# mcu_rev2_full.net
KiCad netlist of a schematic drawn in EAGLE
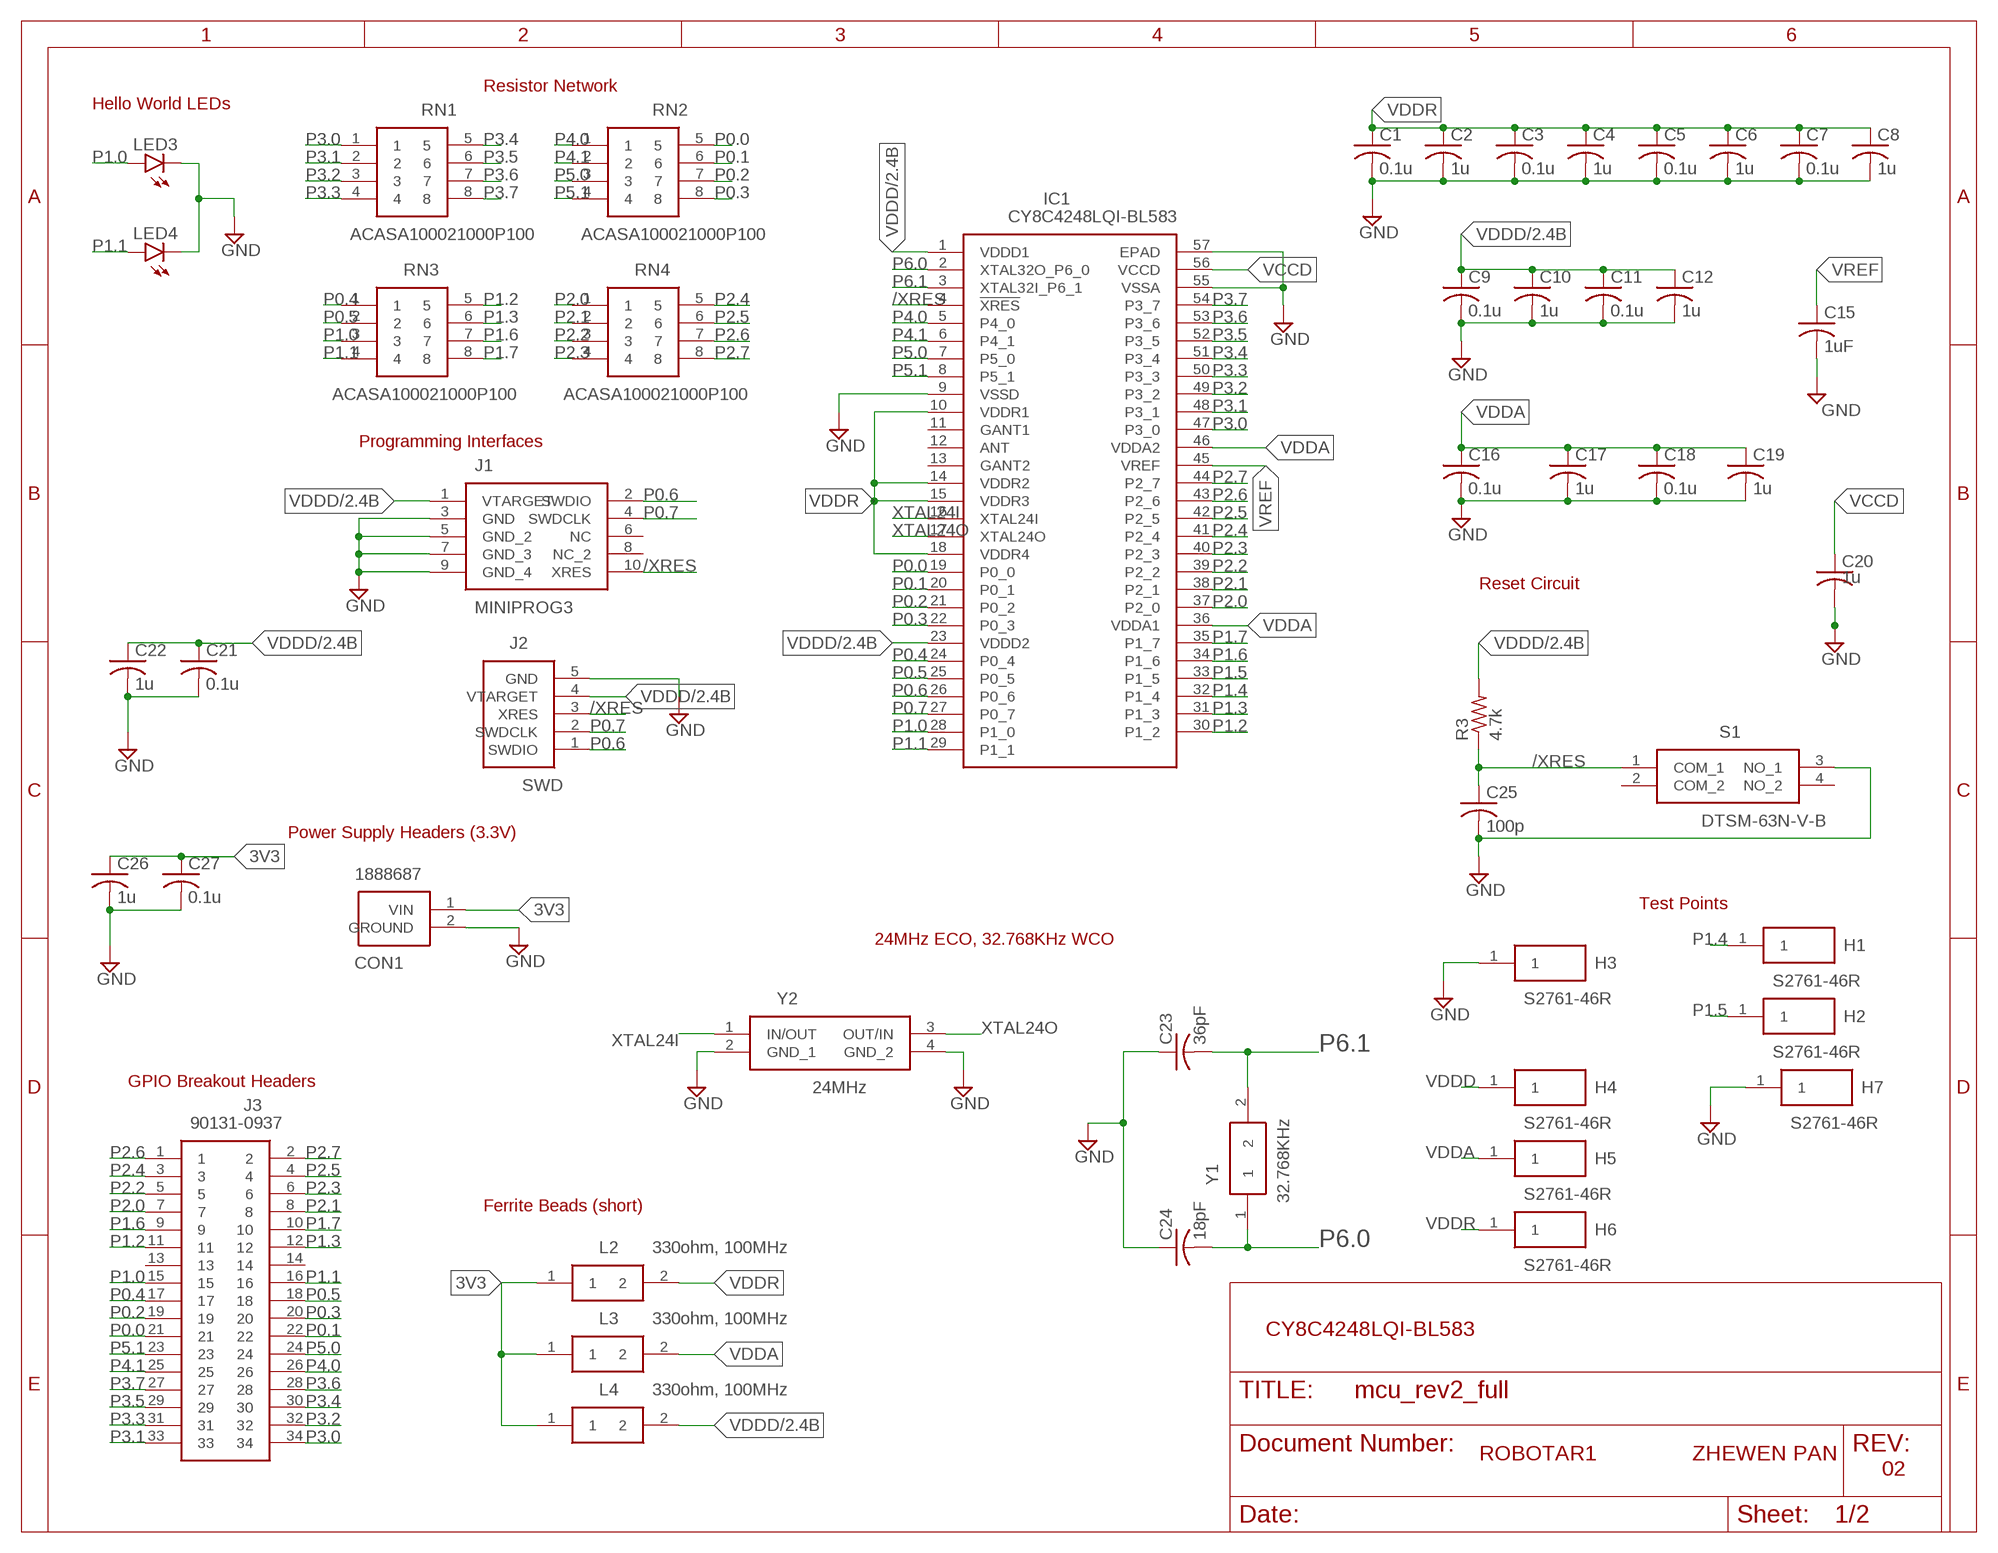
[diagram p0: schematic, sheet 1]
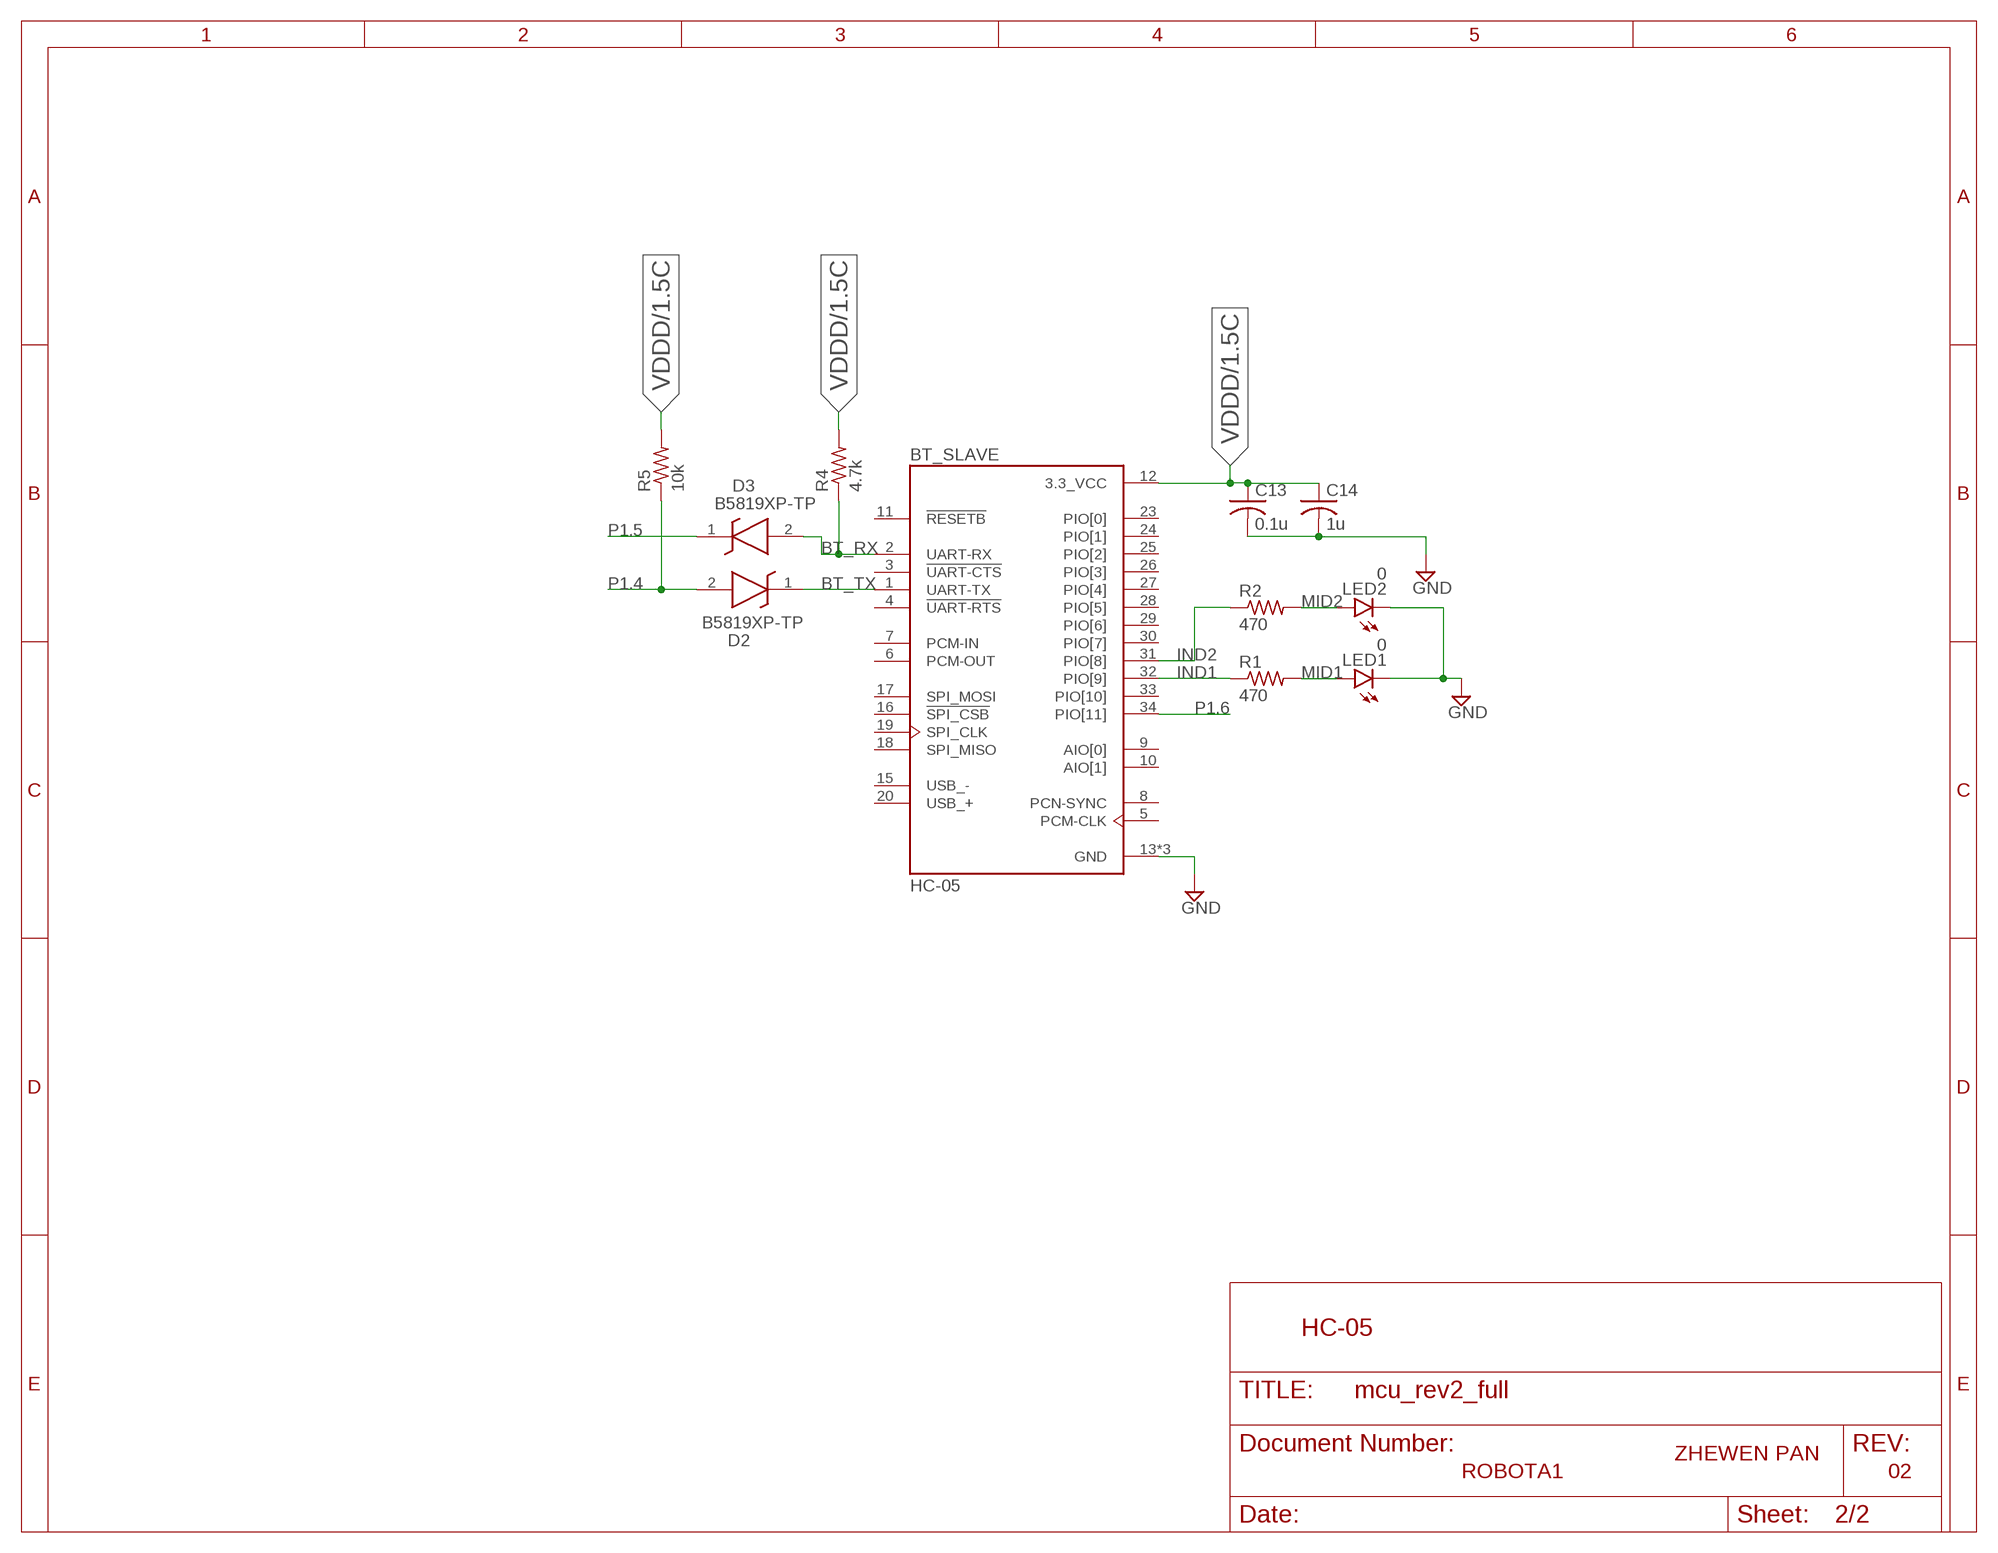
[diagram p1: schematic, sheet 2]

(export (version "E")
  (design (tool "Eeschema 10.0.6"))
  (components
    (comp (ref "C1")
      (value "0.1u")
      (footprint "eagle-import:C0805")
      (libsource (lib "eagle-import") (part "C-USC0805"))
    )
    (comp (ref "C2")
      (value "1u")
      (footprint "eagle-import:C0805")
      (libsource (lib "eagle-import") (part "C-USC0805"))
    )
    (comp (ref "C3")
      (value "0.1u")
      (footprint "eagle-import:C0805")
      (libsource (lib "eagle-import") (part "C-USC0805"))
    )
    (comp (ref "C4")
      (value "1u")
      (footprint "eagle-import:C0805")
      (libsource (lib "eagle-import") (part "C-USC0805"))
    )
    (comp (ref "C5")
      (value "0.1u")
      (footprint "eagle-import:C0805")
      (libsource (lib "eagle-import") (part "C-USC0805"))
    )
    (comp (ref "C6")
      (value "1u")
      (footprint "eagle-import:C0805")
      (libsource (lib "eagle-import") (part "C-USC0805"))
    )
    (comp (ref "C7")
      (value "0.1u")
      (footprint "eagle-import:C0805")
      (libsource (lib "eagle-import") (part "C-USC0805"))
    )
    (comp (ref "C8")
      (value "1u")
      (footprint "eagle-import:C0805")
      (libsource (lib "eagle-import") (part "C-USC0805"))
    )
    (comp (ref "C9")
      (value "0.1u")
      (footprint "eagle-import:C0805")
      (libsource (lib "eagle-import") (part "C-USC0805"))
    )
    (comp (ref "C10")
      (value "1u")
      (footprint "eagle-import:C0805")
      (libsource (lib "eagle-import") (part "C-USC0805"))
    )
    (comp (ref "C11")
      (value "0.1u")
      (footprint "eagle-import:C0805")
      (libsource (lib "eagle-import") (part "C-USC0805"))
    )
    (comp (ref "C12")
      (value "1u")
      (footprint "eagle-import:C0805")
      (libsource (lib "eagle-import") (part "C-USC0805"))
    )
    (comp (ref "C15")
      (value "1uF")
      (footprint "eagle-import:C0805")
      (libsource (lib "eagle-import") (part "C-USC0805"))
    )
    (comp (ref "C16")
      (value "0.1u")
      (footprint "eagle-import:C0805")
      (libsource (lib "eagle-import") (part "C-USC0805"))
    )
    (comp (ref "C17")
      (value "1u")
      (footprint "eagle-import:C0805")
      (libsource (lib "eagle-import") (part "C-USC0805"))
    )
    (comp (ref "C18")
      (value "0.1u")
      (footprint "eagle-import:C0805")
      (libsource (lib "eagle-import") (part "C-USC0805"))
    )
    (comp (ref "C19")
      (value "1u")
      (footprint "eagle-import:C0805")
      (libsource (lib "eagle-import") (part "C-USC0805"))
    )
    (comp (ref "C20")
      (value "1u")
      (footprint "eagle-import:C0805")
      (libsource (lib "eagle-import") (part "C-USC0805"))
    )
    (comp (ref "C21")
      (value "0.1u")
      (footprint "eagle-import:C0805")
      (libsource (lib "eagle-import") (part "C-USC0805"))
    )
    (comp (ref "C22")
      (value "1u")
      (footprint "eagle-import:C0805")
      (libsource (lib "eagle-import") (part "C-USC0805"))
    )
    (comp (ref "C23")
      (value "36pF")
      (footprint "eagle-import:C0805")
      (libsource (lib "eagle-import") (part "C-USC0805"))
    )
    (comp (ref "C24")
      (value "18pF")
      (footprint "eagle-import:C0805")
      (libsource (lib "eagle-import") (part "C-USC0805"))
    )
    (comp (ref "C25")
      (value "100p")
      (footprint "eagle-import:C0805")
      (libsource (lib "eagle-import") (part "C-USC0805"))
    )
    (comp (ref "C26")
      (value "1u")
      (footprint "eagle-import:C0805")
      (libsource (lib "eagle-import") (part "C-USC0805"))
    )
    (comp (ref "C27")
      (value "0.1u")
      (footprint "eagle-import:C0805")
      (libsource (lib "eagle-import") (part "C-USC0805"))
    )
    (comp (ref "CON1")
      (value "1888687")
      (footprint "eagle-import:SHDR2W90P0X508_1X2_1016X950X15")
      (fields (field (name "RS_PART_NUMBER") "8045095"))
      (libsource (lib "eagle-import") (part "1888687"))
    )
    (comp (ref "H1")
      (value "S2761-46R")
      (footprint "eagle-import:S276146R")
      (libsource (lib "eagle-import") (part "S2761-46R"))
    )
    (comp (ref "H2")
      (value "S2761-46R")
      (footprint "eagle-import:S276146R")
      (libsource (lib "eagle-import") (part "S2761-46R"))
    )
    (comp (ref "H3")
      (value "S2761-46R")
      (footprint "eagle-import:S276146R")
      (libsource (lib "eagle-import") (part "S2761-46R"))
    )
    (comp (ref "H4")
      (value "S2761-46R")
      (footprint "eagle-import:S276146R")
      (libsource (lib "eagle-import") (part "S2761-46R"))
    )
    (comp (ref "H5")
      (value "S2761-46R")
      (footprint "eagle-import:S276146R")
      (libsource (lib "eagle-import") (part "S2761-46R"))
    )
    (comp (ref "H6")
      (value "S2761-46R")
      (footprint "eagle-import:S276146R")
      (libsource (lib "eagle-import") (part "S2761-46R"))
    )
    (comp (ref "H7")
      (value "S2761-46R")
      (footprint "eagle-import:S276146R")
      (libsource (lib "eagle-import") (part "S2761-46R"))
    )
    (comp (ref "IC1")
      (value "CY8C4248LQI-BL583")
      (footprint "eagle-import:QFN40P700X700X60-57N")
      (fields (field (name "RS_PART_NUMBER") "1771220P"))
      (libsource (lib "eagle-import") (part "CY8C4248LQI-BL583"))
    )
    (comp (ref "J1")
      (value "MINIPROG3")
      (footprint "eagle-import:FTSH-105-01-L-DV-K")
      (fields
        (field (name "MANUFACTURER_PART_NUMBER") "FTSH-105-01-L-DV-K")
        (field (name "RS_PART_NUMBER") "1592332")
      )
      (libsource (lib "eagle-import") (part "FTSH-105-01-L-DV-K"))
    )
    (comp (ref "J2")
      (value "SWD")
      (footprint "eagle-import:HDRV5W64P0X254_1X5_1255X635X81")
      (fields
        (field (name "MANUFACTURER_PART_NUMBER") "22-23-2051")
        (field (name "RS_PART_NUMBER") "1888757")
      )
      (libsource (lib "eagle-import") (part "22-23-2051"))
    )
    (comp (ref "J3")
      (value "90131-0937")
      (footprint "eagle-import:HDRV34W90P254_2X17_4308X500X56")
      (fields (field (name "RS_PART_NUMBER") "6703569"))
      (libsource (lib "eagle-import") (part "90131-0937"))
    )
    (comp (ref "L2")
      (value "330ohm, 100MHz")
      (footprint "eagle-import:BEADC2012X105N")
      (fields
        (field (name "MANUFACTURER_PART_NUMBER") "BLM21PG331SN1D")
        (field (name "RS_PART_NUMBER") "7241545P")
      )
      (libsource (lib "eagle-import") (part "BLM21PG331SN1D"))
    )
    (comp (ref "L3")
      (value "330ohm, 100MHz")
      (footprint "eagle-import:BEADC2012X105N")
      (fields
        (field (name "MANUFACTURER_PART_NUMBER") "BLM21PG331SN1D")
        (field (name "RS_PART_NUMBER") "7241545P")
      )
      (libsource (lib "eagle-import") (part "BLM21PG331SN1D"))
    )
    (comp (ref "L4")
      (value "330ohm, 100MHz")
      (footprint "eagle-import:BEADC2012X105N")
      (fields
        (field (name "MANUFACTURER_PART_NUMBER") "BLM21PG331SN1D")
        (field (name "RS_PART_NUMBER") "7241545P")
      )
      (libsource (lib "eagle-import") (part "BLM21PG331SN1D"))
    )
    (comp (ref "LED3")
      (value "LEDSML0805")
      (footprint "eagle-import:SML0805")
      (libsource (lib "eagle-import") (part "LEDSML0805"))
    )
    (comp (ref "LED4")
      (value "LEDSML0805")
      (footprint "eagle-import:SML0805")
      (libsource (lib "eagle-import") (part "LEDSML0805"))
    )
    (comp (ref "R3")
      (value "4.7k")
      (footprint "eagle-import:R0805")
      (libsource (lib "eagle-import") (part "R-US_R0805"))
    )
    (comp (ref "RN1")
      (value "ACASA100021000P100")
      (footprint "eagle-import:ACASA100021000P100")
      (fields (field (name "RS_PART_NUMBER") "6845742P"))
      (libsource (lib "eagle-import") (part "ACASA100021000P100"))
    )
    (comp (ref "RN2")
      (value "ACASA100021000P100")
      (footprint "eagle-import:ACASA100021000P100")
      (fields (field (name "RS_PART_NUMBER") "6845742P"))
      (libsource (lib "eagle-import") (part "ACASA100021000P100"))
    )
    (comp (ref "RN3")
      (value "ACASA100021000P100")
      (footprint "eagle-import:ACASA100021000P100")
      (fields (field (name "RS_PART_NUMBER") "6845742P"))
      (libsource (lib "eagle-import") (part "ACASA100021000P100"))
    )
    (comp (ref "RN4")
      (value "ACASA100021000P100")
      (footprint "eagle-import:ACASA100021000P100")
      (fields (field (name "RS_PART_NUMBER") "6845742P"))
      (libsource (lib "eagle-import") (part "ACASA100021000P100"))
    )
    (comp (ref "S1")
      (value "DTSM-63N-V-B")
      (footprint "eagle-import:DTSM63NVB")
      (libsource (lib "eagle-import") (part "DTSM-63N-V-B"))
    )
    (comp (ref "Y1")
      (value "32.768KHz")
      (footprint "eagle-import:ECX-31B")
      (fields (field (name "MANUFACTURER_PART_NUMBER") "ECS-.327-12.5-34B-TR"))
      (libsource (lib "eagle-import") (part "ECS-.327-12.5-34B-TR"))
    )
    (comp (ref "Y2")
      (value "24MHz")
      (footprint "eagle-import:ECS240836QAESTR")
      (fields (field (name "MANUFACTURER_PART_NUMBER") "ECS-240-8-36CKM-TR") (field (name "SPICEPREFIX") "E"))
      (libsource (lib "eagle-import") (part "ECS-240-8-36CKM-TR"))
    )
    (comp (ref "BT_SLAVE")
      (value "HC-05")
      (footprint "eagle-import:XCVR_HC-05")
      (fields (field (name "MF") "Texas Instruments") (field (name "SPICEPREFIX") "X"))
      (libsource (lib "eagle-import") (part "HC-05"))
    )
    (comp (ref "C13")
      (value "0.1u")
      (footprint "eagle-import:C0805")
      (libsource (lib "eagle-import") (part "C-USC0805"))
    )
    (comp (ref "C14")
      (value "1u")
      (footprint "eagle-import:C0805")
      (libsource (lib "eagle-import") (part "C-USC0805"))
    )
    (comp (ref "D2")
      (value "B5819XP-TP")
      (footprint "eagle-import:B5819XPTP")
      (libsource (lib "eagle-import") (part "B5819XP-TP"))
    )
    (comp (ref "D3")
      (value "B5819XP-TP")
      (footprint "eagle-import:B5819XPTP")
      (libsource (lib "eagle-import") (part "B5819XP-TP"))
    )
    (comp (ref "LED1")
      (value "0")
      (footprint "eagle-import:SML0805")
      (libsource (lib "eagle-import") (part "LEDSML0805"))
    )
    (comp (ref "LED2")
      (value "0")
      (footprint "eagle-import:SML0805")
      (libsource (lib "eagle-import") (part "LEDSML0805"))
    )
    (comp (ref "R1")
      (value "470")
      (footprint "eagle-import:R0805")
      (libsource (lib "eagle-import") (part "R-US_R0805"))
    )
    (comp (ref "R2")
      (value "470")
      (footprint "eagle-import:R0805")
      (libsource (lib "eagle-import") (part "R-US_R0805"))
    )
    (comp (ref "R4")
      (value "4.7k")
      (footprint "eagle-import:R0805")
      (libsource (lib "eagle-import") (part "R-US_R0805"))
    )
    (comp (ref "R5")
      (value "10k")
      (footprint "eagle-import:R0805")
      (libsource (lib "eagle-import") (part "R-US_R0805"))
    )
  )
  (nets
    (net (code "1") (name "3V3") (class "Default")
      (node (ref "C26") (pin "1") (pinfunction "1_1") (pintype "passive"))
      (node (ref "C27") (pin "1") (pinfunction "1_1") (pintype "passive"))
      (node (ref "CON1") (pin "1") (pinfunction "VIN_1") (pintype "bidirectional"))
      (node (ref "L2") (pin "1") (pinfunction "1_1") (pintype "bidirectional"))
      (node (ref "L3") (pin "1") (pinfunction "1_1") (pintype "bidirectional"))
      (node (ref "L4") (pin "1") (pinfunction "1_1") (pintype "bidirectional"))
    )
    (net (code "2") (name "BT_RX") (class "Default")
      (node (ref "BT_SLAVE") (pin "2") (pinfunction "UART-RX_2") (pintype "input"))
      (node (ref "D3") (pin "2") (pinfunction "+_2") (pintype "bidirectional"))
      (node (ref "R4") (pin "1") (pinfunction "1_1") (pintype "passive"))
    )
    (net (code "3") (name "BT_TX") (class "Default")
      (node (ref "BT_SLAVE") (pin "1") (pinfunction "UART-TX_1") (pintype "output"))
      (node (ref "D2") (pin "1") (pinfunction "-_1") (pintype "bidirectional"))
    )
    (net (code "4") (name "GND") (class "Default")
      (node (ref "BT_SLAVE") (pin "13") (pinfunction "GND_13") (pintype "power_in"))
      (node (ref "BT_SLAVE") (pin "21") (pinfunction "GND_21") (pintype "power_in"))
      (node (ref "BT_SLAVE") (pin "22") (pinfunction "GND_22") (pintype "power_in"))
      (node (ref "C1") (pin "2") (pinfunction "2_2") (pintype "passive"))
      (node (ref "C10") (pin "2") (pinfunction "2_2") (pintype "passive"))
      (node (ref "C11") (pin "2") (pinfunction "2_2") (pintype "passive"))
      (node (ref "C12") (pin "2") (pinfunction "2_2") (pintype "passive"))
      (node (ref "C13") (pin "2") (pinfunction "2_2") (pintype "passive"))
      (node (ref "C14") (pin "2") (pinfunction "2_2") (pintype "passive"))
      (node (ref "C15") (pin "2") (pinfunction "2_2") (pintype "passive"))
      (node (ref "C16") (pin "2") (pinfunction "2_2") (pintype "passive"))
      (node (ref "C17") (pin "2") (pinfunction "2_2") (pintype "passive"))
      (node (ref "C18") (pin "2") (pinfunction "2_2") (pintype "passive"))
      (node (ref "C19") (pin "2") (pinfunction "2_2") (pintype "passive"))
      (node (ref "C2") (pin "2") (pinfunction "2_2") (pintype "passive"))
      (node (ref "C20") (pin "2") (pinfunction "2_2") (pintype "passive"))
      (node (ref "C21") (pin "2") (pinfunction "2_2") (pintype "passive"))
      (node (ref "C22") (pin "2") (pinfunction "2_2") (pintype "passive"))
      (node (ref "C23") (pin "1") (pinfunction "1_1") (pintype "passive"))
      (node (ref "C24") (pin "1") (pinfunction "1_1") (pintype "passive"))
      (node (ref "C25") (pin "2") (pinfunction "2_2") (pintype "passive"))
      (node (ref "C26") (pin "2") (pinfunction "2_2") (pintype "passive"))
      (node (ref "C27") (pin "2") (pinfunction "2_2") (pintype "passive"))
      (node (ref "C3") (pin "2") (pinfunction "2_2") (pintype "passive"))
      (node (ref "C4") (pin "2") (pinfunction "2_2") (pintype "passive"))
      (node (ref "C5") (pin "2") (pinfunction "2_2") (pintype "passive"))
      (node (ref "C6") (pin "2") (pinfunction "2_2") (pintype "passive"))
      (node (ref "C7") (pin "2") (pinfunction "2_2") (pintype "passive"))
      (node (ref "C8") (pin "2") (pinfunction "2_2") (pintype "passive"))
      (node (ref "C9") (pin "2") (pinfunction "2_2") (pintype "passive"))
      (node (ref "CON1") (pin "2") (pinfunction "GROUND_2") (pintype "bidirectional"))
      (node (ref "H3") (pin "1") (pinfunction "1_1") (pintype "bidirectional"))
      (node (ref "H7") (pin "1") (pinfunction "1_1") (pintype "bidirectional"))
      (node (ref "IC1") (pin "55") (pinfunction "VSSA_55") (pintype "bidirectional"))
      (node (ref "IC1") (pin "57") (pinfunction "EPAD_57") (pintype "bidirectional"))
      (node (ref "IC1") (pin "9") (pinfunction "VSSD_9") (pintype "bidirectional"))
      (node (ref "J1") (pin "3") (pinfunction "GND_3") (pintype "bidirectional"))
      (node (ref "J1") (pin "5") (pinfunction "GND_2_5") (pintype "bidirectional"))
      (node (ref "J1") (pin "7") (pinfunction "GND_3_7") (pintype "bidirectional"))
      (node (ref "J1") (pin "9") (pinfunction "GND_4_9") (pintype "bidirectional"))
      (node (ref "J2") (pin "5") (pinfunction "GND_5") (pintype "bidirectional"))
      (node (ref "LED1") (pin "C") (pinfunction "C_C") (pintype "passive"))
      (node (ref "LED2") (pin "C") (pinfunction "C_C") (pintype "passive"))
      (node (ref "LED3") (pin "C") (pinfunction "C_C") (pintype "passive"))
      (node (ref "LED4") (pin "C") (pinfunction "C_C") (pintype "passive"))
      (node (ref "S1") (pin "3") (pinfunction "NO_1_3") (pintype "bidirectional"))
      (node (ref "Y2") (pin "2") (pinfunction "GND_1_2") (pintype "bidirectional"))
      (node (ref "Y2") (pin "4") (pinfunction "GND_2_4") (pintype "bidirectional"))
    )
    (net (code "5") (name "IND1") (class "Default")
      (node (ref "BT_SLAVE") (pin "32") (pinfunction "PIO[9]_32") (pintype "bidirectional"))
      (node (ref "R1") (pin "1") (pinfunction "1_1") (pintype "passive"))
    )
    (net (code "6") (name "IND2") (class "Default")
      (node (ref "BT_SLAVE") (pin "31") (pinfunction "PIO[8]_31") (pintype "bidirectional"))
      (node (ref "R2") (pin "1") (pinfunction "1_1") (pintype "passive"))
    )
    (net (code "7") (name "MID1") (class "Default")
      (node (ref "LED1") (pin "A") (pinfunction "A_A") (pintype "passive"))
      (node (ref "R1") (pin "2") (pinfunction "2_2") (pintype "passive"))
    )
    (net (code "8") (name "MID2") (class "Default")
      (node (ref "LED2") (pin "A") (pinfunction "A_A") (pintype "passive"))
      (node (ref "R2") (pin "2") (pinfunction "2_2") (pintype "passive"))
    )
    (net (code "9") (name "P0.0") (class "Default")
      (node (ref "IC1") (pin "19") (pinfunction "P0_0_19") (pintype "bidirectional"))
      (node (ref "J3") (pin "21") (pinfunction "21_21") (pintype "bidirectional"))
      (node (ref "RN2") (pin "5") (pinfunction "5_5") (pintype "bidirectional"))
    )
    (net (code "10") (name "P0.1") (class "Default")
      (node (ref "IC1") (pin "20") (pinfunction "P0_1_20") (pintype "bidirectional"))
      (node (ref "J3") (pin "22") (pinfunction "22_22") (pintype "bidirectional"))
      (node (ref "RN2") (pin "6") (pinfunction "6_6") (pintype "bidirectional"))
    )
    (net (code "11") (name "P0.2") (class "Default")
      (node (ref "IC1") (pin "21") (pinfunction "P0_2_21") (pintype "bidirectional"))
      (node (ref "J3") (pin "19") (pinfunction "19_19") (pintype "bidirectional"))
      (node (ref "RN2") (pin "7") (pinfunction "7_7") (pintype "bidirectional"))
    )
    (net (code "12") (name "P0.3") (class "Default")
      (node (ref "IC1") (pin "22") (pinfunction "P0_3_22") (pintype "bidirectional"))
      (node (ref "J3") (pin "20") (pinfunction "20_20") (pintype "bidirectional"))
      (node (ref "RN2") (pin "8") (pinfunction "8_8") (pintype "bidirectional"))
    )
    (net (code "13") (name "P0.4") (class "Default")
      (node (ref "IC1") (pin "24") (pinfunction "P0_4_24") (pintype "bidirectional"))
      (node (ref "J3") (pin "17") (pinfunction "17_17") (pintype "bidirectional"))
      (node (ref "RN3") (pin "1") (pinfunction "1_1") (pintype "bidirectional"))
    )
    (net (code "14") (name "P0.5") (class "Default")
      (node (ref "IC1") (pin "25") (pinfunction "P0_5_25") (pintype "bidirectional"))
      (node (ref "J3") (pin "18") (pinfunction "18_18") (pintype "bidirectional"))
      (node (ref "RN3") (pin "2") (pinfunction "2_2") (pintype "bidirectional"))
    )
    (net (code "15") (name "P0.6") (class "Default")
      (node (ref "IC1") (pin "26") (pinfunction "P0_6_26") (pintype "bidirectional"))
      (node (ref "J1") (pin "2") (pinfunction "SWDIO_2") (pintype "bidirectional"))
      (node (ref "J2") (pin "1") (pinfunction "SWDIO_1") (pintype "bidirectional"))
    )
    (net (code "16") (name "P0.7") (class "Default")
      (node (ref "IC1") (pin "27") (pinfunction "P0_7_27") (pintype "bidirectional"))
      (node (ref "J1") (pin "4") (pinfunction "SWDCLK_4") (pintype "bidirectional"))
      (node (ref "J2") (pin "2") (pinfunction "SWDCLK_2") (pintype "bidirectional"))
    )
    (net (code "17") (name "P1.0") (class "Default")
      (node (ref "IC1") (pin "28") (pinfunction "P1_0_28") (pintype "bidirectional"))
      (node (ref "J3") (pin "15") (pinfunction "15_15") (pintype "bidirectional"))
      (node (ref "LED3") (pin "A") (pinfunction "A_A") (pintype "passive"))
      (node (ref "RN3") (pin "3") (pinfunction "3_3") (pintype "bidirectional"))
    )
    (net (code "18") (name "P1.1") (class "Default")
      (node (ref "IC1") (pin "29") (pinfunction "P1_1_29") (pintype "bidirectional"))
      (node (ref "J3") (pin "16") (pinfunction "16_16") (pintype "bidirectional"))
      (node (ref "LED4") (pin "A") (pinfunction "A_A") (pintype "passive"))
      (node (ref "RN3") (pin "4") (pinfunction "4_4") (pintype "bidirectional"))
    )
    (net (code "19") (name "P1.2") (class "Default")
      (node (ref "IC1") (pin "30") (pinfunction "P1_2_30") (pintype "bidirectional"))
      (node (ref "J3") (pin "11") (pinfunction "11_11") (pintype "bidirectional"))
      (node (ref "RN3") (pin "5") (pinfunction "5_5") (pintype "bidirectional"))
    )
    (net (code "20") (name "P1.3") (class "Default")
      (node (ref "IC1") (pin "31") (pinfunction "P1_3_31") (pintype "bidirectional"))
      (node (ref "J3") (pin "12") (pinfunction "12_12") (pintype "bidirectional"))
      (node (ref "RN3") (pin "6") (pinfunction "6_6") (pintype "bidirectional"))
    )
    (net (code "21") (name "P1.4") (class "Default")
      (node (ref "D2") (pin "2") (pinfunction "+_2") (pintype "bidirectional"))
      (node (ref "H1") (pin "1") (pinfunction "1_1") (pintype "bidirectional"))
      (node (ref "IC1") (pin "32") (pinfunction "P1_4_32") (pintype "bidirectional"))
      (node (ref "R5") (pin "1") (pinfunction "1_1") (pintype "passive"))
    )
    (net (code "22") (name "P1.5") (class "Default")
      (node (ref "D3") (pin "1") (pinfunction "-_1") (pintype "bidirectional"))
      (node (ref "H2") (pin "1") (pinfunction "1_1") (pintype "bidirectional"))
      (node (ref "IC1") (pin "33") (pinfunction "P1_5_33") (pintype "bidirectional"))
    )
    (net (code "23") (name "P1.6") (class "Default")
      (node (ref "BT_SLAVE") (pin "34") (pinfunction "PIO[11]_34") (pintype "bidirectional"))
      (node (ref "IC1") (pin "34") (pinfunction "P1_6_34") (pintype "bidirectional"))
      (node (ref "J3") (pin "9") (pinfunction "9_9") (pintype "bidirectional"))
      (node (ref "RN3") (pin "7") (pinfunction "7_7") (pintype "bidirectional"))
    )
    (net (code "24") (name "P1.7") (class "Default")
      (node (ref "IC1") (pin "35") (pinfunction "P1_7_35") (pintype "bidirectional"))
      (node (ref "J3") (pin "10") (pinfunction "10_10") (pintype "bidirectional"))
      (node (ref "RN3") (pin "8") (pinfunction "8_8") (pintype "bidirectional"))
    )
    (net (code "25") (name "P2.0") (class "Default")
      (node (ref "IC1") (pin "37") (pinfunction "P2_0_37") (pintype "bidirectional"))
      (node (ref "J3") (pin "7") (pinfunction "7_7") (pintype "bidirectional"))
      (node (ref "RN4") (pin "1") (pinfunction "1_1") (pintype "bidirectional"))
    )
    (net (code "26") (name "P2.1") (class "Default")
      (node (ref "IC1") (pin "38") (pinfunction "P2_1_38") (pintype "bidirectional"))
      (node (ref "J3") (pin "8") (pinfunction "8_8") (pintype "bidirectional"))
      (node (ref "RN4") (pin "2") (pinfunction "2_2") (pintype "bidirectional"))
    )
    (net (code "27") (name "P2.2") (class "Default")
      (node (ref "IC1") (pin "39") (pinfunction "P2_2_39") (pintype "bidirectional"))
      (node (ref "J3") (pin "5") (pinfunction "5_5") (pintype "bidirectional"))
      (node (ref "RN4") (pin "3") (pinfunction "3_3") (pintype "bidirectional"))
    )
    (net (code "28") (name "P2.3") (class "Default")
      (node (ref "IC1") (pin "40") (pinfunction "P2_3_40") (pintype "bidirectional"))
      (node (ref "J3") (pin "6") (pinfunction "6_6") (pintype "bidirectional"))
      (node (ref "RN4") (pin "4") (pinfunction "4_4") (pintype "bidirectional"))
    )
    (net (code "29") (name "P2.4") (class "Default")
      (node (ref "IC1") (pin "41") (pinfunction "P2_4_41") (pintype "bidirectional"))
      (node (ref "J3") (pin "3") (pinfunction "3_3") (pintype "bidirectional"))
      (node (ref "RN4") (pin "5") (pinfunction "5_5") (pintype "bidirectional"))
    )
    (net (code "30") (name "P2.5") (class "Default")
      (node (ref "IC1") (pin "42") (pinfunction "P2_5_42") (pintype "bidirectional"))
      (node (ref "J3") (pin "4") (pinfunction "4_4") (pintype "bidirectional"))
      (node (ref "RN4") (pin "6") (pinfunction "6_6") (pintype "bidirectional"))
    )
    (net (code "31") (name "P2.6") (class "Default")
      (node (ref "IC1") (pin "43") (pinfunction "P2_6_43") (pintype "bidirectional"))
      (node (ref "J3") (pin "1") (pinfunction "1_1") (pintype "bidirectional"))
      (node (ref "RN4") (pin "7") (pinfunction "7_7") (pintype "bidirectional"))
    )
    (net (code "32") (name "P2.7") (class "Default")
      (node (ref "IC1") (pin "44") (pinfunction "P2_7_44") (pintype "bidirectional"))
      (node (ref "J3") (pin "2") (pinfunction "2_2") (pintype "bidirectional"))
      (node (ref "RN4") (pin "8") (pinfunction "8_8") (pintype "bidirectional"))
    )
    (net (code "33") (name "P3.0") (class "Default")
      (node (ref "IC1") (pin "47") (pinfunction "P3_0_47") (pintype "bidirectional"))
      (node (ref "J3") (pin "34") (pinfunction "34_34") (pintype "bidirectional"))
      (node (ref "RN1") (pin "1") (pinfunction "1_1") (pintype "bidirectional"))
    )
    (net (code "34") (name "P3.1") (class "Default")
      (node (ref "IC1") (pin "48") (pinfunction "P3_1_48") (pintype "bidirectional"))
      (node (ref "J3") (pin "33") (pinfunction "33_33") (pintype "bidirectional"))
      (node (ref "RN1") (pin "2") (pinfunction "2_2") (pintype "bidirectional"))
    )
    (net (code "35") (name "P3.2") (class "Default")
      (node (ref "IC1") (pin "49") (pinfunction "P3_2_49") (pintype "bidirectional"))
      (node (ref "J3") (pin "32") (pinfunction "32_32") (pintype "bidirectional"))
      (node (ref "RN1") (pin "3") (pinfunction "3_3") (pintype "bidirectional"))
    )
    (net (code "36") (name "P3.3") (class "Default")
      (node (ref "IC1") (pin "50") (pinfunction "P3_3_50") (pintype "bidirectional"))
      (node (ref "J3") (pin "31") (pinfunction "31_31") (pintype "bidirectional"))
      (node (ref "RN1") (pin "4") (pinfunction "4_4") (pintype "bidirectional"))
    )
    (net (code "37") (name "P3.4") (class "Default")
      (node (ref "IC1") (pin "51") (pinfunction "P3_4_51") (pintype "bidirectional"))
      (node (ref "J3") (pin "30") (pinfunction "30_30") (pintype "bidirectional"))
      (node (ref "RN1") (pin "5") (pinfunction "5_5") (pintype "bidirectional"))
    )
    (net (code "38") (name "P3.5") (class "Default")
      (node (ref "IC1") (pin "52") (pinfunction "P3_5_52") (pintype "bidirectional"))
      (node (ref "J3") (pin "29") (pinfunction "29_29") (pintype "bidirectional"))
      (node (ref "RN1") (pin "6") (pinfunction "6_6") (pintype "bidirectional"))
    )
    (net (code "39") (name "P3.6") (class "Default")
      (node (ref "IC1") (pin "53") (pinfunction "P3_6_53") (pintype "bidirectional"))
      (node (ref "J3") (pin "28") (pinfunction "28_28") (pintype "bidirectional"))
      (node (ref "RN1") (pin "7") (pinfunction "7_7") (pintype "bidirectional"))
    )
    (net (code "40") (name "P3.7") (class "Default")
      (node (ref "IC1") (pin "54") (pinfunction "P3_7_54") (pintype "bidirectional"))
      (node (ref "J3") (pin "27") (pinfunction "27_27") (pintype "bidirectional"))
      (node (ref "RN1") (pin "8") (pinfunction "8_8") (pintype "bidirectional"))
    )
    (net (code "41") (name "P4.0") (class "Default")
      (node (ref "IC1") (pin "5") (pinfunction "P4_0_5") (pintype "bidirectional"))
      (node (ref "J3") (pin "26") (pinfunction "26_26") (pintype "bidirectional"))
      (node (ref "RN2") (pin "1") (pinfunction "1_1") (pintype "bidirectional"))
    )
    (net (code "42") (name "P4.1") (class "Default")
      (node (ref "IC1") (pin "6") (pinfunction "P4_1_6") (pintype "bidirectional"))
      (node (ref "J3") (pin "25") (pinfunction "25_25") (pintype "bidirectional"))
      (node (ref "RN2") (pin "2") (pinfunction "2_2") (pintype "bidirectional"))
    )
    (net (code "43") (name "P5.0") (class "Default")
      (node (ref "IC1") (pin "7") (pinfunction "P5_0_7") (pintype "bidirectional"))
      (node (ref "J3") (pin "24") (pinfunction "24_24") (pintype "bidirectional"))
      (node (ref "RN2") (pin "3") (pinfunction "3_3") (pintype "bidirectional"))
    )
    (net (code "44") (name "P5.1") (class "Default")
      (node (ref "IC1") (pin "8") (pinfunction "P5_1_8") (pintype "bidirectional"))
      (node (ref "J3") (pin "23") (pinfunction "23_23") (pintype "bidirectional"))
      (node (ref "RN2") (pin "4") (pinfunction "4_4") (pintype "bidirectional"))
    )
    (net (code "45") (name "P6.0") (class "Default")
      (node (ref "C24") (pin "2") (pinfunction "2_2") (pintype "passive"))
      (node (ref "IC1") (pin "2") (pinfunction "XTAL32O_P6_0_2") (pintype "bidirectional"))
      (node (ref "Y1") (pin "1") (pinfunction "1_1") (pintype "bidirectional"))
    )
    (net (code "46") (name "P6.1") (class "Default")
      (node (ref "C23") (pin "2") (pinfunction "2_2") (pintype "passive"))
      (node (ref "IC1") (pin "3") (pinfunction "XTAL32I_P6_1_3") (pintype "bidirectional"))
      (node (ref "Y1") (pin "2") (pinfunction "2_2") (pintype "bidirectional"))
    )
    (net (code "47") (name "VCCD") (class "Default")
      (node (ref "C20") (pin "1") (pinfunction "1_1") (pintype "passive"))
      (node (ref "IC1") (pin "56") (pinfunction "VCCD_56") (pintype "bidirectional"))
    )
    (net (code "48") (name "VDDA") (class "Default")
      (node (ref "C16") (pin "1") (pinfunction "1_1") (pintype "passive"))
      (node (ref "C17") (pin "1") (pinfunction "1_1") (pintype "passive"))
      (node (ref "C18") (pin "1") (pinfunction "1_1") (pintype "passive"))
      (node (ref "C19") (pin "1") (pinfunction "1_1") (pintype "passive"))
      (node (ref "H5") (pin "1") (pinfunction "1_1") (pintype "bidirectional"))
      (node (ref "IC1") (pin "36") (pinfunction "VDDA1_36") (pintype "bidirectional"))
      (node (ref "IC1") (pin "46") (pinfunction "VDDA2_46") (pintype "bidirectional"))
      (node (ref "L3") (pin "2") (pinfunction "2_2") (pintype "bidirectional"))
    )
    (net (code "49") (name "VDDD") (class "Default")
      (node (ref "BT_SLAVE") (pin "12") (pinfunction "3.3_VCC_12") (pintype "power_in"))
      (node (ref "C10") (pin "1") (pinfunction "1_1") (pintype "passive"))
      (node (ref "C11") (pin "1") (pinfunction "1_1") (pintype "passive"))
      (node (ref "C12") (pin "1") (pinfunction "1_1") (pintype "passive"))
      (node (ref "C13") (pin "1") (pinfunction "1_1") (pintype "passive"))
      (node (ref "C14") (pin "1") (pinfunction "1_1") (pintype "passive"))
      (node (ref "C21") (pin "1") (pinfunction "1_1") (pintype "passive"))
      (node (ref "C22") (pin "1") (pinfunction "1_1") (pintype "passive"))
      (node (ref "C9") (pin "1") (pinfunction "1_1") (pintype "passive"))
      (node (ref "H4") (pin "1") (pinfunction "1_1") (pintype "bidirectional"))
      (node (ref "IC1") (pin "1") (pinfunction "VDDD1_1") (pintype "bidirectional"))
      (node (ref "IC1") (pin "23") (pinfunction "VDDD2_23") (pintype "bidirectional"))
      (node (ref "J1") (pin "1") (pinfunction "VTARGET_1") (pintype "bidirectional"))
      (node (ref "J2") (pin "4") (pinfunction "VTARGET_4") (pintype "bidirectional"))
      (node (ref "L4") (pin "2") (pinfunction "2_2") (pintype "bidirectional"))
      (node (ref "R3") (pin "2") (pinfunction "2_2") (pintype "passive"))
      (node (ref "R4") (pin "2") (pinfunction "2_2") (pintype "passive"))
      (node (ref "R5") (pin "2") (pinfunction "2_2") (pintype "passive"))
    )
    (net (code "50") (name "VDDR") (class "Default")
      (node (ref "C1") (pin "1") (pinfunction "1_1") (pintype "passive"))
      (node (ref "C2") (pin "1") (pinfunction "1_1") (pintype "passive"))
      (node (ref "C3") (pin "1") (pinfunction "1_1") (pintype "passive"))
      (node (ref "C4") (pin "1") (pinfunction "1_1") (pintype "passive"))
      (node (ref "C5") (pin "1") (pinfunction "1_1") (pintype "passive"))
      (node (ref "C6") (pin "1") (pinfunction "1_1") (pintype "passive"))
      (node (ref "C7") (pin "1") (pinfunction "1_1") (pintype "passive"))
      (node (ref "C8") (pin "1") (pinfunction "1_1") (pintype "passive"))
      (node (ref "H6") (pin "1") (pinfunction "1_1") (pintype "bidirectional"))
      (node (ref "IC1") (pin "10") (pinfunction "VDDR1_10") (pintype "bidirectional"))
      (node (ref "IC1") (pin "14") (pinfunction "VDDR2_14") (pintype "bidirectional"))
      (node (ref "IC1") (pin "15") (pinfunction "VDDR3_15") (pintype "bidirectional"))
      (node (ref "IC1") (pin "18") (pinfunction "VDDR4_18") (pintype "bidirectional"))
      (node (ref "L2") (pin "2") (pinfunction "2_2") (pintype "bidirectional"))
    )
    (net (code "51") (name "VREF") (class "Default")
      (node (ref "C15") (pin "1") (pinfunction "1_1") (pintype "passive"))
      (node (ref "IC1") (pin "45") (pinfunction "VREF_45") (pintype "bidirectional"))
    )
    (net (code "52") (name "XTAL24I") (class "Default")
      (node (ref "IC1") (pin "16") (pinfunction "XTAL24I_16") (pintype "bidirectional"))
      (node (ref "Y2") (pin "1") (pinfunction "IN/OUT_1") (pintype "bidirectional"))
    )
    (net (code "53") (name "XTAL24O") (class "Default")
      (node (ref "IC1") (pin "17") (pinfunction "XTAL24O_17") (pintype "bidirectional"))
      (node (ref "Y2") (pin "3") (pinfunction "OUT/IN_3") (pintype "bidirectional"))
    )
    (net (code "54") (name "unconnected-(BT_SLAVE-AIO[0]-Pad9)") (class "Default")
      (node (ref "BT_SLAVE") (pin "9") (pinfunction "AIO[0]_9") (pintype "bidirectional"))
    )
    (net (code "55") (name "unconnected-(BT_SLAVE-AIO[1]-Pad10)") (class "Default")
      (node (ref "BT_SLAVE") (pin "10") (pinfunction "AIO[1]_10") (pintype "bidirectional"))
    )
    (net (code "56") (name "unconnected-(BT_SLAVE-PCM-CLK-Pad5)") (class "Default")
      (node (ref "BT_SLAVE") (pin "5") (pinfunction "PCM-CLK_5") (pintype "bidirectional"))
    )
    (net (code "57") (name "unconnected-(BT_SLAVE-PCM-IN-Pad7)") (class "Default")
      (node (ref "BT_SLAVE") (pin "7") (pinfunction "PCM-IN_7") (pintype "input"))
    )
    (net (code "58") (name "unconnected-(BT_SLAVE-PCM-OUT-Pad6)") (class "Default")
      (node (ref "BT_SLAVE") (pin "6") (pinfunction "PCM-OUT_6") (pintype "output"))
    )
    (net (code "59") (name "unconnected-(BT_SLAVE-PCN-SYNC-Pad8)") (class "Default")
      (node (ref "BT_SLAVE") (pin "8") (pinfunction "PCN-SYNC_8") (pintype "bidirectional"))
    )
    (net (code "60") (name "unconnected-(BT_SLAVE-PIO[0]-Pad23)") (class "Default")
      (node (ref "BT_SLAVE") (pin "23") (pinfunction "PIO[0]_23") (pintype "bidirectional"))
    )
    (net (code "61") (name "unconnected-(BT_SLAVE-PIO[1]-Pad24)") (class "Default")
      (node (ref "BT_SLAVE") (pin "24") (pinfunction "PIO[1]_24") (pintype "bidirectional"))
    )
    (net (code "62") (name "unconnected-(BT_SLAVE-PIO[2]-Pad25)") (class "Default")
      (node (ref "BT_SLAVE") (pin "25") (pinfunction "PIO[2]_25") (pintype "bidirectional"))
    )
    (net (code "63") (name "unconnected-(BT_SLAVE-PIO[3]-Pad26)") (class "Default")
      (node (ref "BT_SLAVE") (pin "26") (pinfunction "PIO[3]_26") (pintype "bidirectional"))
    )
    (net (code "64") (name "unconnected-(BT_SLAVE-PIO[4]-Pad27)") (class "Default")
      (node (ref "BT_SLAVE") (pin "27") (pinfunction "PIO[4]_27") (pintype "bidirectional"))
    )
    (net (code "65") (name "unconnected-(BT_SLAVE-PIO[5]-Pad28)") (class "Default")
      (node (ref "BT_SLAVE") (pin "28") (pinfunction "PIO[5]_28") (pintype "bidirectional"))
    )
    (net (code "66") (name "unconnected-(BT_SLAVE-PIO[6]-Pad29)") (class "Default")
      (node (ref "BT_SLAVE") (pin "29") (pinfunction "PIO[6]_29") (pintype "bidirectional"))
    )
    (net (code "67") (name "unconnected-(BT_SLAVE-PIO[7]-Pad30)") (class "Default")
      (node (ref "BT_SLAVE") (pin "30") (pinfunction "PIO[7]_30") (pintype "bidirectional"))
    )
    (net (code "68") (name "unconnected-(BT_SLAVE-PIO[10]-Pad33)") (class "Default")
      (node (ref "BT_SLAVE") (pin "33") (pinfunction "PIO[10]_33") (pintype "bidirectional"))
    )
    (net (code "69") (name "unconnected-(BT_SLAVE-SPI_CLK-Pad19)") (class "Default")
      (node (ref "BT_SLAVE") (pin "19") (pinfunction "SPI_CLK_19") (pintype "input"))
    )
    (net (code "70") (name "unconnected-(BT_SLAVE-SPI_MISO-Pad18)") (class "Default")
      (node (ref "BT_SLAVE") (pin "18") (pinfunction "SPI_MISO_18") (pintype "output"))
    )
    (net (code "71") (name "unconnected-(BT_SLAVE-SPI_MOSI-Pad17)") (class "Default")
      (node (ref "BT_SLAVE") (pin "17") (pinfunction "SPI_MOSI_17") (pintype "input"))
    )
    (net (code "72") (name "unconnected-(BT_SLAVE-USB_+-Pad20)") (class "Default")
      (node (ref "BT_SLAVE") (pin "20") (pinfunction "USB_+_20") (pintype "bidirectional"))
    )
    (net (code "73") (name "unconnected-(BT_SLAVE-USB_--Pad15)") (class "Default")
      (node (ref "BT_SLAVE") (pin "15") (pinfunction "USB_-_15") (pintype "bidirectional"))
    )
    (net (code "74") (name "unconnected-(BT_SLAVE-~{RESETB}-Pad11)") (class "Default")
      (node (ref "BT_SLAVE") (pin "11") (pinfunction "~{RESETB}_11") (pintype "input"))
    )
    (net (code "75") (name "unconnected-(BT_SLAVE-~{SPI_CSB}-Pad16)") (class "Default")
      (node (ref "BT_SLAVE") (pin "16") (pinfunction "~{SPI_CSB}_16") (pintype "input"))
    )
    (net (code "76") (name "unconnected-(BT_SLAVE-~{UART-CTS}-Pad3)") (class "Default")
      (node (ref "BT_SLAVE") (pin "3") (pinfunction "~{UART-CTS}_3") (pintype "input"))
    )
    (net (code "77") (name "unconnected-(BT_SLAVE-~{UART-RTS}-Pad4)") (class "Default")
      (node (ref "BT_SLAVE") (pin "4") (pinfunction "~{UART-RTS}_4") (pintype "output"))
    )
    (net (code "78") (name "unconnected-(IC1-ANT-Pad12)") (class "Default")
      (node (ref "IC1") (pin "12") (pinfunction "ANT_12") (pintype "bidirectional"))
    )
    (net (code "79") (name "unconnected-(IC1-GANT1-Pad11)") (class "Default")
      (node (ref "IC1") (pin "11") (pinfunction "GANT1_11") (pintype "bidirectional"))
    )
    (net (code "80") (name "unconnected-(IC1-GANT2-Pad13)") (class "Default")
      (node (ref "IC1") (pin "13") (pinfunction "GANT2_13") (pintype "bidirectional"))
    )
    (net (code "81") (name "unconnected-(J1-NC-Pad6)") (class "Default")
      (node (ref "J1") (pin "6") (pinfunction "NC_6") (pintype "bidirectional"))
    )
    (net (code "82") (name "unconnected-(J1-NC_2-Pad8)") (class "Default")
      (node (ref "J1") (pin "8") (pinfunction "NC_2_8") (pintype "bidirectional"))
    )
    (net (code "83") (name "unconnected-(J3-Pad13)") (class "Default")
      (node (ref "J3") (pin "13") (pinfunction "13_13") (pintype "bidirectional"))
    )
    (net (code "84") (name "unconnected-(J3-Pad14)") (class "Default")
      (node (ref "J3") (pin "14") (pinfunction "14_14") (pintype "bidirectional"))
    )
    (net (code "85") (name "unconnected-(S1-COM_2-Pad2)") (class "Default")
      (node (ref "S1") (pin "2") (pinfunction "COM_2_2") (pintype "bidirectional"))
    )
    (net (code "86") (name "unconnected-(S1-NO_2-Pad4)") (class "Default")
      (node (ref "S1") (pin "4") (pinfunction "NO_2_4") (pintype "bidirectional"))
    )
    (net (code "87") (name "{slash}XRES") (class "Default")
      (node (ref "C25") (pin "1") (pinfunction "1_1") (pintype "passive"))
      (node (ref "IC1") (pin "4") (pinfunction "~{XRES}_4") (pintype "bidirectional"))
      (node (ref "J1") (pin "10") (pinfunction "XRES_10") (pintype "bidirectional"))
      (node (ref "J2") (pin "3") (pinfunction "XRES_3") (pintype "bidirectional"))
      (node (ref "R3") (pin "1") (pinfunction "1_1") (pintype "passive"))
      (node (ref "S1") (pin "1") (pinfunction "COM_1_1") (pintype "bidirectional"))
    )
  )
)
